# 6DOF.net
KiCad netlist of a schematic drawn in Altium Designer
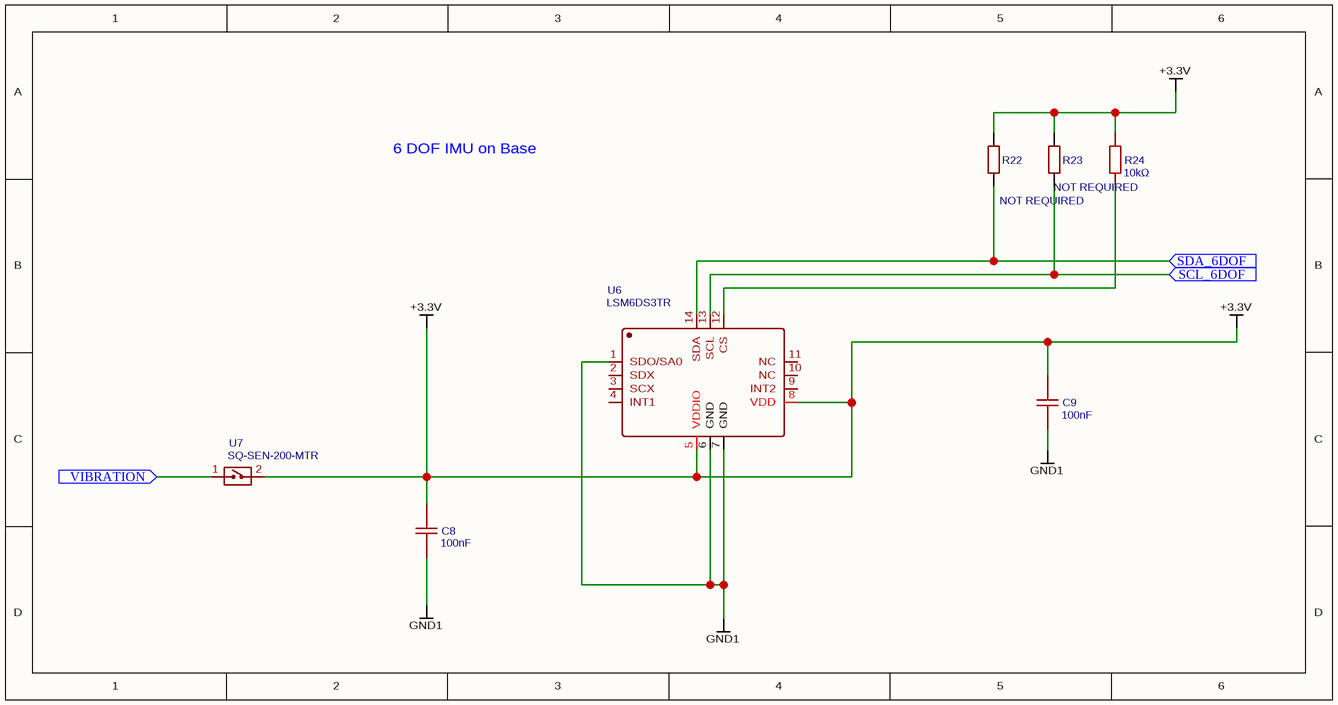
[diagram p0: 6DOF.schdoc]

(export (version "E")
  (design (tool "Eeschema 10.0.6"))
  (components
    (comp (ref "C8")
      (value "100nF")
      (fields
        (field (name "BOM_SUPPLIER PART") "C519981")
        (field (name "BOM_MANUFACTURER PART") "CC0805KRX7R8BB104")
        (field (name "CONTRIBUTOR") "LCSC")
      )
      (libsource (lib "altium-import") (part "root_1_100nF_"))
    )
    (comp (ref "C9")
      (value "100nF")
      (fields
        (field (name "BOM_SUPPLIER PART") "C519981")
        (field (name "BOM_MANUFACTURER PART") "CC0805KRX7R8BB104")
        (field (name "CONTRIBUTOR") "LCSC")
      )
      (libsource (lib "altium-import") (part "root_1_100nF_"))
    )
    (comp (ref "R22")
      (value "NOT REQUIRED")
      (fields
        (field (name "BOM_MANUFACTURER PART") "0805W8J0472T5E")
        (field (name "BOM_SUPPLIER PART") "C26022")
      )
      (libsource (lib "altium-import") (part "root_1_NOT REQUIRED_"))
    )
    (comp (ref "R23")
      (value "NOT REQUIRED")
      (fields
        (field (name "BOM_MANUFACTURER PART") "0805W8J0472T5E")
        (field (name "BOM_SUPPLIER PART") "C26022")
      )
      (libsource (lib "altium-import") (part "root_1_NOT REQUIRED_"))
    )
    (comp (ref "R24")
      (value "10kΩ")
      (fields
        (field (name "BOM_SUPPLIER PART") "C332266")
        (field (name "BOM_MANUFACTURER PART") "TR0805D10KP0550")
        (field (name "CONTRIBUTOR") "LCSC")
      )
      (libsource (lib "altium-import") (part "root_1_10kΩ_"))
    )
    (comp (ref "U6")
      (value "LSM6DS3TR")
      (fields (field (name "BOM_SUPPLIER PART") "C95230") (field (name "CONTRIBUTOR") "LCSC"))
      (libsource (lib "altium-import") (part "root_0_LSM6DS3TR_"))
    )
    (comp (ref "U7")
      (value "SQ-SEN-200-MTR")
      (fields (field (name "BOM_SUPPLIER PART") "C2687703") (field (name "CONTRIBUTOR") "LCSC"))
      (libsource (lib "altium-import") (part "root_0_SQ-SEN-200-MTR_"))
    )
  )
  (nets
    (net (code "1") (name "+3.3V") (class "Default")
      (node (ref "C8") (pin "2") (pinfunction "2_2") (pintype "passive"))
      (node (ref "C9") (pin "2") (pinfunction "2_2") (pintype "passive"))
      (node (ref "R22") (pin "2") (pinfunction "2_2") (pintype "passive"))
      (node (ref "R23") (pin "2") (pinfunction "2_2") (pintype "passive"))
      (node (ref "R24") (pin "2") (pinfunction "2_2") (pintype "passive"))
      (node (ref "U6") (pin "5") (pinfunction "VDDIO_5") (pintype "passive"))
      (node (ref "U6") (pin "8") (pinfunction "VDD_8") (pintype "passive"))
      (node (ref "U7") (pin "2") (pinfunction "2_2") (pintype "passive"))
    )
    (net (code "2") (name "/SCL_6DOF") (class "Default")
      (node (ref "R23") (pin "1") (pinfunction "1_1") (pintype "passive"))
      (node (ref "U6") (pin "13") (pinfunction "SCL_13") (pintype "passive"))
    )
    (net (code "3") (name "/SDA_6DOF") (class "Default")
      (node (ref "R22") (pin "1") (pinfunction "1_1") (pintype "passive"))
      (node (ref "U6") (pin "14") (pinfunction "SDA_14") (pintype "passive"))
    )
    (net (code "4") (name "/VIBRATION") (class "Default")
      (node (ref "U7") (pin "1") (pinfunction "1_1") (pintype "passive"))
    )
    (net (code "5") (name "GND1") (class "Default")
      (node (ref "C8") (pin "1") (pinfunction "1_1") (pintype "passive"))
      (node (ref "C9") (pin "1") (pinfunction "1_1") (pintype "passive"))
      (node (ref "U6") (pin "1") (pinfunction "SDO/SA0_1") (pintype "passive"))
      (node (ref "U6") (pin "6") (pinfunction "GND_6") (pintype "passive"))
      (node (ref "U6") (pin "7") (pinfunction "GND_7") (pintype "passive"))
    )
    (net (code "6") (name "Net-(U6-CS)") (class "Default")
      (node (ref "R24") (pin "1") (pinfunction "1_1") (pintype "passive"))
      (node (ref "U6") (pin "12") (pinfunction "CS_12") (pintype "passive"))
    )
    (net (code "7") (name "unconnected-(U6-INT1-Pad4)") (class "Default")
      (node (ref "U6") (pin "4") (pinfunction "INT1_4") (pintype "passive"))
    )
    (net (code "8") (name "unconnected-(U6-INT2-Pad9)") (class "Default")
      (node (ref "U6") (pin "9") (pinfunction "INT2_9") (pintype "passive"))
    )
    (net (code "9") (name "unconnected-(U6-NC-Pad10)") (class "Default")
      (node (ref "U6") (pin "10") (pinfunction "NC_10") (pintype "passive"))
    )
    (net (code "10") (name "unconnected-(U6-NC-Pad11)") (class "Default")
      (node (ref "U6") (pin "11") (pinfunction "NC_11") (pintype "passive"))
    )
    (net (code "11") (name "unconnected-(U6-SCX-Pad3)") (class "Default")
      (node (ref "U6") (pin "3") (pinfunction "SCX_3") (pintype "passive"))
    )
    (net (code "12") (name "unconnected-(U6-SDX-Pad2)") (class "Default")
      (node (ref "U6") (pin "2") (pinfunction "SDX_2") (pintype "passive"))
    )
  )
)
